# design.net
KiCad netlist of a schematic drawn in Altium Designer
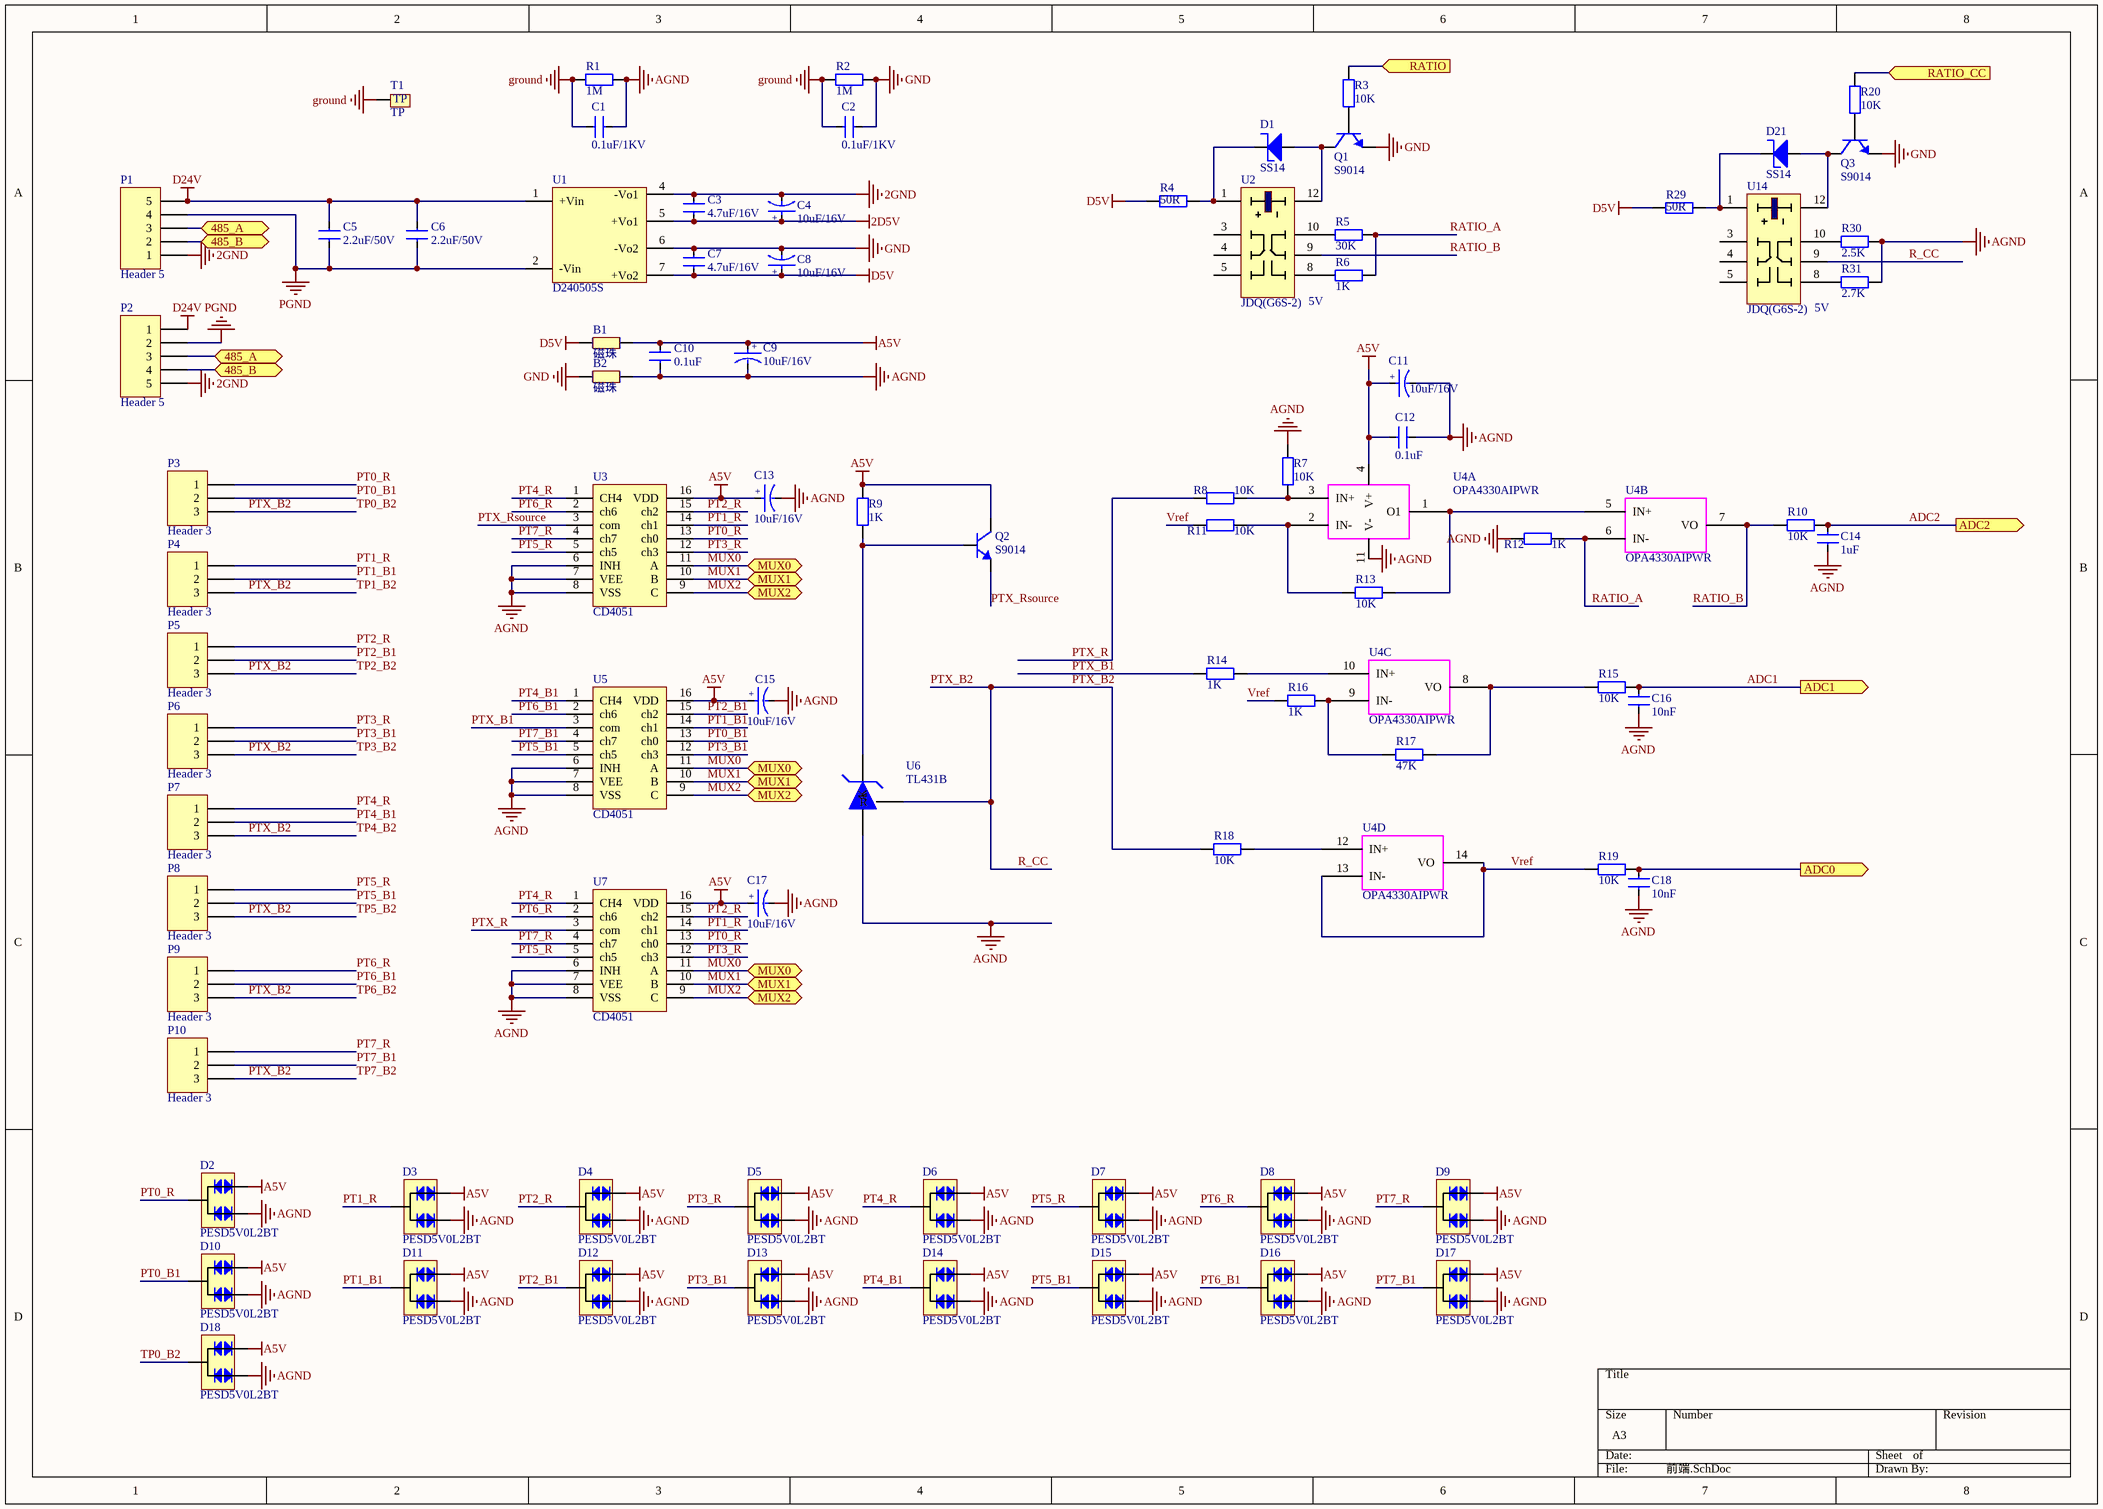
[diagram p0: 前端.SchDoc]

(export (version "E")
  (design (tool "Eeschema 10.0.6"))
  (components
    (comp (ref "B1") (value "磁珠") (footprint "0603L") (libsource (lib "lib_AD") (part "BEAD")))
    (comp (ref "B2") (value "磁珠") (footprint "0603L") (libsource (lib "lib_AD") (part "BEAD")))
    (comp (ref "C1")
      (value "0.1uF/1KV")
      (footprint "RAD0.2")
      (description "普通小电容")
      (libsource (lib "") (part "CAP_1"))
    )
    (comp (ref "C2")
      (value "0.1uF/1KV")
      (footprint "RAD0.2")
      (description "普通小电容")
      (libsource (lib "") (part "CAP_1"))
    )
    (comp (ref "C3")
      (value "4.7uF/16V")
      (footprint "0805C")
      (description "普通小电容")
      (libsource (lib "lib_AD") (part "CAP"))
    )
    (comp (ref "C4")
      (value "10uF/16V")
      (footprint "3216C")
      (description "钽电容")
      (libsource (lib "lib_AD") (part "CAP-T"))
    )
    (comp (ref "C5")
      (value "2.2uF/50V")
      (footprint "0805C")
      (description "普通小电容")
      (libsource (lib "lib_AD") (part "CAP"))
    )
    (comp (ref "C6")
      (value "2.2uF/50V")
      (footprint "0805C")
      (description "普通小电容")
      (libsource (lib "lib_AD") (part "CAP"))
    )
    (comp (ref "C7")
      (value "4.7uF/16V")
      (footprint "0805C")
      (description "普通小电容")
      (libsource (lib "lib_AD") (part "CAP"))
    )
    (comp (ref "C8")
      (value "10uF/16V")
      (footprint "3216C")
      (description "钽电容")
      (libsource (lib "lib_AD") (part "CAP-T"))
    )
    (comp (ref "C9")
      (value "10uF/16V")
      (footprint "3216C")
      (description "钽电容")
      (libsource (lib "lib_AD") (part "CAP-T"))
    )
    (comp (ref "C10")
      (value "0.1uF")
      (footprint "0603C")
      (description "普通小电容")
      (libsource (lib "lib_AD") (part "CAP"))
    )
    (comp (ref "C11")
      (value "10uF/16V")
      (footprint "3216C")
      (description "钽电容")
      (libsource (lib "lib_AD") (part "CAP-T"))
    )
    (comp (ref "C12")
      (value "0.1uF")
      (footprint "0603C")
      (description "普通小电容")
      (libsource (lib "lib_AD") (part "CAP"))
    )
    (comp (ref "C13")
      (value "10uF/16V")
      (footprint "3216C")
      (description "钽电容")
      (libsource (lib "lib_AD") (part "CAP-T"))
    )
    (comp (ref "C14")
      (value "1uF")
      (footprint "0603C")
      (description "普通小电容")
      (libsource (lib "") (part "CAP_1"))
    )
    (comp (ref "C15")
      (value "10uF/16V")
      (footprint "3216C")
      (description "钽电容")
      (libsource (lib "lib_AD") (part "CAP-T"))
    )
    (comp (ref "C16")
      (value "10nF")
      (footprint "0603C")
      (description "普通小电容")
      (libsource (lib "") (part "CAP_1"))
    )
    (comp (ref "C17")
      (value "10uF/16V")
      (footprint "3216C")
      (description "钽电容")
      (libsource (lib "lib_AD") (part "CAP-T"))
    )
    (comp (ref "C18")
      (value "10nF")
      (footprint "0603C")
      (description "普通小电容")
      (libsource (lib "") (part "CAP_1"))
    )
    (comp (ref "D1")
      (value "SS14")
      (footprint "SOD123")
      (description "肖特基二极管")
      (libsource (lib "lib_AD") (part "D-S"))
    )
    (comp (ref "D2")
      (value "PESD5V0L2BT")
      (footprint "SOT23A")
      (description "schottky diod")
      (libsource (lib "R_C_L_D") (part "PESD5V0L2BT"))
    )
    (comp (ref "D3")
      (value "PESD5V0L2BT")
      (footprint "SOT23A")
      (description "schottky diod")
      (libsource (lib "R_C_L_D") (part "PESD5V0L2BT"))
    )
    (comp (ref "D4")
      (value "PESD5V0L2BT")
      (footprint "SOT23A")
      (description "schottky diod")
      (libsource (lib "R_C_L_D") (part "PESD5V0L2BT"))
    )
    (comp (ref "D5")
      (value "PESD5V0L2BT")
      (footprint "SOT23A")
      (description "schottky diod")
      (libsource (lib "R_C_L_D") (part "PESD5V0L2BT"))
    )
    (comp (ref "D6")
      (value "PESD5V0L2BT")
      (footprint "SOT23A")
      (description "schottky diod")
      (libsource (lib "R_C_L_D") (part "PESD5V0L2BT"))
    )
    (comp (ref "D7")
      (value "PESD5V0L2BT")
      (footprint "SOT23A")
      (description "schottky diod")
      (libsource (lib "R_C_L_D") (part "PESD5V0L2BT"))
    )
    (comp (ref "D8")
      (value "PESD5V0L2BT")
      (footprint "SOT23A")
      (description "schottky diod")
      (libsource (lib "R_C_L_D") (part "PESD5V0L2BT"))
    )
    (comp (ref "D9")
      (value "PESD5V0L2BT")
      (footprint "SOT23A")
      (description "schottky diod")
      (libsource (lib "R_C_L_D") (part "PESD5V0L2BT"))
    )
    (comp (ref "D10")
      (value "PESD5V0L2BT")
      (footprint "SOT23A")
      (description "schottky diod")
      (libsource (lib "R_C_L_D") (part "PESD5V0L2BT"))
    )
    (comp (ref "D11")
      (value "PESD5V0L2BT")
      (footprint "SOT23A")
      (description "schottky diod")
      (libsource (lib "R_C_L_D") (part "PESD5V0L2BT"))
    )
    (comp (ref "D12")
      (value "PESD5V0L2BT")
      (footprint "SOT23A")
      (description "schottky diod")
      (libsource (lib "R_C_L_D") (part "PESD5V0L2BT"))
    )
    (comp (ref "D13")
      (value "PESD5V0L2BT")
      (footprint "SOT23A")
      (description "schottky diod")
      (libsource (lib "R_C_L_D") (part "PESD5V0L2BT"))
    )
    (comp (ref "D14")
      (value "PESD5V0L2BT")
      (footprint "SOT23A")
      (description "schottky diod")
      (libsource (lib "R_C_L_D") (part "PESD5V0L2BT"))
    )
    (comp (ref "D15")
      (value "PESD5V0L2BT")
      (footprint "SOT23A")
      (description "schottky diod")
      (libsource (lib "R_C_L_D") (part "PESD5V0L2BT"))
    )
    (comp (ref "D16")
      (value "PESD5V0L2BT")
      (footprint "SOT23A")
      (description "schottky diod")
      (libsource (lib "R_C_L_D") (part "PESD5V0L2BT"))
    )
    (comp (ref "D17")
      (value "PESD5V0L2BT")
      (footprint "SOT23A")
      (description "schottky diod")
      (libsource (lib "R_C_L_D") (part "PESD5V0L2BT"))
    )
    (comp (ref "D18")
      (value "PESD5V0L2BT")
      (footprint "SOT23A")
      (description "schottky diod")
      (libsource (lib "R_C_L_D") (part "PESD5V0L2BT"))
    )
    (comp (ref "D21")
      (value "SS14")
      (footprint "SOD123")
      (description "肖特基二极管")
      (libsource (lib "lib_AD") (part "D-S"))
    )
    (comp (ref "P1")
      (value "Header 5")
      (footprint "KF2DEG-3.81-5")
      (description "Header, 5-Pin")
      (fields (field (name "PUBLISHER") "Altium Limited"))
      (libsource (lib "") (part "Header 5_1"))
    )
    (comp (ref "P2")
      (value "Header 5")
      (footprint "KF2DEG-3.81-5")
      (description "Header, 5-Pin")
      (fields (field (name "PUBLISHER") "Altium Limited"))
      (libsource (lib "lib_AD") (part "Header 5"))
    )
    (comp (ref "P3")
      (value "Header 3")
      (footprint "KF2DEG-3.81-3")
      (description "Header, 3-Pin")
      (fields (field (name "PUBLISHER") "Altium Limited"))
      (libsource (lib "Header") (part "Header 3"))
    )
    (comp (ref "P4")
      (value "Header 3")
      (footprint "KF2DEG-3.81-3")
      (description "Header, 3-Pin")
      (fields (field (name "PUBLISHER") "Altium Limited"))
      (libsource (lib "Header") (part "Header 3"))
    )
    (comp (ref "P5")
      (value "Header 3")
      (footprint "KF2DEG-3.81-3")
      (description "Header, 3-Pin")
      (fields (field (name "PUBLISHER") "Altium Limited"))
      (libsource (lib "Header") (part "Header 3"))
    )
    (comp (ref "P6")
      (value "Header 3")
      (footprint "KF2DEG-3.81-3")
      (description "Header, 3-Pin")
      (fields (field (name "PUBLISHER") "Altium Limited"))
      (libsource (lib "Header") (part "Header 3"))
    )
    (comp (ref "P7")
      (value "Header 3")
      (footprint "KF2DEG-3.81-3")
      (description "Header, 3-Pin")
      (fields (field (name "PUBLISHER") "Altium Limited"))
      (libsource (lib "Header") (part "Header 3"))
    )
    (comp (ref "P8")
      (value "Header 3")
      (footprint "KF2DEG-3.81-3")
      (description "Header, 3-Pin")
      (fields (field (name "PUBLISHER") "Altium Limited"))
      (libsource (lib "Header") (part "Header 3"))
    )
    (comp (ref "P9")
      (value "Header 3")
      (footprint "KF2DEG-3.81-3")
      (description "Header, 3-Pin")
      (fields (field (name "PUBLISHER") "Altium Limited"))
      (libsource (lib "Header") (part "Header 3"))
    )
    (comp (ref "P10")
      (value "Header 3")
      (footprint "KF2DEG-3.81-3")
      (description "Header, 3-Pin")
      (fields (field (name "PUBLISHER") "Altium Limited"))
      (libsource (lib "Header") (part "Header 3"))
    )
    (comp (ref "Q1")
      (value "S9014")
      (footprint "SOT23A")
      (description "NPN三极管")
      (fields (field (name "PUBLISHER") "Altium Limited"))
      (libsource (lib "lib_AD") (part "NPN"))
    )
    (comp (ref "Q2")
      (value "S9014")
      (footprint "SOT23A")
      (description "NPN三极管")
      (fields (field (name "PUBLISHER") "Altium Limited"))
      (libsource (lib "lib_AD") (part "NPN"))
    )
    (comp (ref "Q3")
      (value "S9014")
      (footprint "SOT23A")
      (description "NPN三极管")
      (fields (field (name "PUBLISHER") "Altium Limited"))
      (libsource (lib "lib_AD") (part "NPN"))
    )
    (comp (ref "R1")
      (value "1M")
      (footprint "0805R")
      (description "普通电阻")
      (libsource (lib "") (part "RES_2"))
    )
    (comp (ref "R2")
      (value "1M")
      (footprint "0805R")
      (description "普通电阻")
      (libsource (lib "") (part "RES_2"))
    )
    (comp (ref "R3")
      (value "10K")
      (footprint "0603R")
      (description "普通电阻")
      (libsource (lib "") (part "RES_1"))
    )
    (comp (ref "R4")
      (value "50R")
      (footprint "0603R")
      (description "普通电阻")
      (libsource (lib "lib_AD") (part "RES"))
    )
    (comp (ref "R5")
      (value "30K")
      (footprint "0603R")
      (description "普通电阻")
      (libsource (lib "") (part "RES_1"))
    )
    (comp (ref "R6")
      (value "1K")
      (footprint "0603R")
      (description "普通电阻")
      (libsource (lib "") (part "RES_1"))
    )
    (comp (ref "R7")
      (value "10K")
      (footprint "0603R")
      (description "普通电阻")
      (libsource (lib "") (part "RES_1"))
    )
    (comp (ref "R8")
      (value "10K")
      (footprint "0603R")
      (description "普通电阻")
      (libsource (lib "lib_AD") (part "RES"))
    )
    (comp (ref "R9")
      (value "1K")
      (footprint "0603R")
      (description "普通电阻")
      (libsource (lib "") (part "RES_3"))
    )
    (comp (ref "R10")
      (value "10K")
      (footprint "0603R")
      (description "普通电阻")
      (libsource (lib "") (part "RES_2"))
    )
    (comp (ref "R11")
      (value "10K")
      (footprint "0603R")
      (description "普通电阻")
      (libsource (lib "lib_AD") (part "RES"))
    )
    (comp (ref "R12")
      (value "1K")
      (footprint "0603R")
      (description "普通电阻")
      (libsource (lib "lib_AD") (part "RES"))
    )
    (comp (ref "R13")
      (value "10K")
      (footprint "0603R")
      (description "普通电阻")
      (libsource (lib "lib_AD") (part "RES"))
    )
    (comp (ref "R14")
      (value "1K")
      (footprint "0603R")
      (description "普通电阻")
      (libsource (lib "lib_AD") (part "RES"))
    )
    (comp (ref "R15")
      (value "10K")
      (footprint "0603R")
      (description "普通电阻")
      (libsource (lib "") (part "RES_2"))
    )
    (comp (ref "R16")
      (value "1K")
      (footprint "0603R")
      (description "普通电阻")
      (libsource (lib "lib_AD") (part "RES"))
    )
    (comp (ref "R17")
      (value "47K")
      (footprint "0603R")
      (description "普通电阻")
      (libsource (lib "") (part "RES_2"))
    )
    (comp (ref "R18")
      (value "10K")
      (footprint "0603R")
      (description "普通电阻")
      (libsource (lib "lib_AD") (part "RES"))
    )
    (comp (ref "R19")
      (value "10K")
      (footprint "0603R")
      (description "普通电阻")
      (libsource (lib "") (part "RES_2"))
    )
    (comp (ref "R20")
      (value "10K")
      (footprint "0603R")
      (description "普通电阻")
      (libsource (lib "") (part "RES_1"))
    )
    (comp (ref "R29")
      (value "50R")
      (footprint "0603R")
      (description "普通电阻")
      (libsource (lib "lib_AD") (part "RES"))
    )
    (comp (ref "R30")
      (value "2.5K")
      (footprint "0603R")
      (description "普通电阻")
      (libsource (lib "") (part "RES_1"))
    )
    (comp (ref "R31")
      (value "2.7K")
      (footprint "0603R")
      (description "普通电阻")
      (libsource (lib "") (part "RES_1"))
    )
    (comp (ref "T1")
      (value "TP")
      (footprint "TP1")
      (description "testpoint")
      (libsource (lib "lib_AD") (part "TP"))
    )
    (comp (ref "U1")
      (value "D240505S")
      (footprint "D240505S-2W")
      (description "24V转双5V隔离DCDC")
      (libsource (lib "lib_AD") (part "D240505S-2W"))
    )
    (comp (ref "U2")
      (value "JDQ(G6S-2)")
      (footprint "JDQ-G6S-2")
      (description "继电器（G6S-2 5VDC）")
      (libsource (lib "Misc") (part "JDQ(G6S-2)"))
    )
    (comp (ref "U3")
      (value "CD4051")
      (footprint "SOP16")
      (description "模拟多路复用器")
      (libsource (lib "lib_AD") (part "CD4051"))
    )
    (comp (ref "U4")
      (value "OPA4330AIPWR")
      (footprint "TSSOP14-65")
      (description "输出轨到轨，4运放")
      (libsource (lib "lib_AD") (part "OPA4330"))
    )
    (comp (ref "U5")
      (value "CD4051")
      (footprint "SOP16")
      (description "模拟多路复用器")
      (libsource (lib "lib_AD") (part "CD4051"))
    )
    (comp (ref "U6")
      (value "TL431B")
      (footprint "SOT-89")
      (description "TL431")
      (libsource (lib "lib_AD") (part "TL431"))
    )
    (comp (ref "U7")
      (value "CD4051")
      (footprint "SOP16")
      (description "模拟多路复用器")
      (libsource (lib "lib_AD") (part "CD4051"))
    )
    (comp (ref "U14")
      (value "JDQ(G6S-2)")
      (footprint "JDQ-G6S-2")
      (description "继电器（G6S-2 5VDC）")
      (libsource (lib "Misc") (part "JDQ(G6S-2)"))
    )
  )
  (nets
    (net (code "1") (name "/485_A") (class "Default")
      (node (ref "P1") (pin "3") (pinfunction "3_3") (pintype "passive"))
      (node (ref "P2") (pin "3") (pinfunction "3_3") (pintype "passive"))
    )
    (net (code "2") (name "/485_B") (class "Default")
      (node (ref "P1") (pin "2") (pinfunction "2_2") (pintype "passive"))
      (node (ref "P2") (pin "4") (pinfunction "4_4") (pintype "passive"))
    )
    (net (code "3") (name "/ADC0") (class "Default")
      (node (ref "C18") (pin "1") (pinfunction "1_1") (pintype "passive"))
      (node (ref "R19") (pin "2") (pinfunction "2_2") (pintype "passive"))
    )
    (net (code "4") (name "/ADC1") (class "Default")
      (node (ref "C16") (pin "1") (pinfunction "1_1") (pintype "passive"))
      (node (ref "R15") (pin "2") (pinfunction "2_2") (pintype "passive"))
    )
    (net (code "5") (name "/ADC2") (class "Default")
      (node (ref "C14") (pin "1") (pinfunction "1_1") (pintype "passive"))
      (node (ref "R10") (pin "2") (pinfunction "2_2") (pintype "passive"))
    )
    (net (code "6") (name "/MUX0") (class "Default")
      (node (ref "U3") (pin "11") (pinfunction "A_11") (pintype "passive"))
      (node (ref "U5") (pin "11") (pinfunction "A_11") (pintype "passive"))
      (node (ref "U7") (pin "11") (pinfunction "A_11") (pintype "passive"))
    )
    (net (code "7") (name "/MUX1") (class "Default")
      (node (ref "U3") (pin "10") (pinfunction "B_10") (pintype "passive"))
      (node (ref "U5") (pin "10") (pinfunction "B_10") (pintype "passive"))
      (node (ref "U7") (pin "10") (pinfunction "B_10") (pintype "passive"))
    )
    (net (code "8") (name "/MUX2") (class "Default")
      (node (ref "U3") (pin "9") (pinfunction "C_9") (pintype "passive"))
      (node (ref "U5") (pin "9") (pinfunction "C_9") (pintype "passive"))
      (node (ref "U7") (pin "9") (pinfunction "C_9") (pintype "passive"))
    )
    (net (code "9") (name "/PT0_B1") (class "Default")
      (node (ref "D10") (pin "3") (pinfunction "3_3") (pintype "passive"))
      (node (ref "P3") (pin "2") (pinfunction "2_2") (pintype "passive"))
      (node (ref "U5") (pin "13") (pinfunction "ch0_13") (pintype "passive"))
    )
    (net (code "10") (name "/PT0_R") (class "Default")
      (node (ref "D2") (pin "3") (pinfunction "3_3") (pintype "passive"))
      (node (ref "P3") (pin "1") (pinfunction "1_1") (pintype "passive"))
      (node (ref "U3") (pin "13") (pinfunction "ch0_13") (pintype "passive"))
      (node (ref "U7") (pin "13") (pinfunction "ch0_13") (pintype "passive"))
    )
    (net (code "11") (name "/PT1_B1") (class "Default")
      (node (ref "D11") (pin "3") (pinfunction "3_3") (pintype "passive"))
      (node (ref "P4") (pin "2") (pinfunction "2_2") (pintype "passive"))
      (node (ref "U5") (pin "14") (pinfunction "ch1_14") (pintype "passive"))
    )
    (net (code "12") (name "/PT1_R") (class "Default")
      (node (ref "D3") (pin "3") (pinfunction "3_3") (pintype "passive"))
      (node (ref "P4") (pin "1") (pinfunction "1_1") (pintype "passive"))
      (node (ref "U3") (pin "14") (pinfunction "ch1_14") (pintype "passive"))
      (node (ref "U7") (pin "14") (pinfunction "ch1_14") (pintype "passive"))
    )
    (net (code "13") (name "/PT2_B1") (class "Default")
      (node (ref "D12") (pin "3") (pinfunction "3_3") (pintype "passive"))
      (node (ref "P5") (pin "2") (pinfunction "2_2") (pintype "passive"))
      (node (ref "U5") (pin "15") (pinfunction "ch2_15") (pintype "passive"))
    )
    (net (code "14") (name "/PT2_R") (class "Default")
      (node (ref "D4") (pin "3") (pinfunction "3_3") (pintype "passive"))
      (node (ref "P5") (pin "1") (pinfunction "1_1") (pintype "passive"))
      (node (ref "U3") (pin "15") (pinfunction "ch2_15") (pintype "passive"))
      (node (ref "U7") (pin "15") (pinfunction "ch2_15") (pintype "passive"))
    )
    (net (code "15") (name "/PT3_B1") (class "Default")
      (node (ref "D13") (pin "3") (pinfunction "3_3") (pintype "passive"))
      (node (ref "P6") (pin "2") (pinfunction "2_2") (pintype "passive"))
      (node (ref "U5") (pin "12") (pinfunction "ch3_12") (pintype "passive"))
    )
    (net (code "16") (name "/PT3_R") (class "Default")
      (node (ref "D5") (pin "3") (pinfunction "3_3") (pintype "passive"))
      (node (ref "P6") (pin "1") (pinfunction "1_1") (pintype "passive"))
      (node (ref "U3") (pin "12") (pinfunction "ch3_12") (pintype "passive"))
      (node (ref "U7") (pin "12") (pinfunction "ch3_12") (pintype "passive"))
    )
    (net (code "17") (name "/PT4_B1") (class "Default")
      (node (ref "D14") (pin "3") (pinfunction "3_3") (pintype "passive"))
      (node (ref "P7") (pin "2") (pinfunction "2_2") (pintype "passive"))
      (node (ref "U5") (pin "1") (pinfunction "CH4_1") (pintype "passive"))
    )
    (net (code "18") (name "/PT4_R") (class "Default")
      (node (ref "D6") (pin "3") (pinfunction "3_3") (pintype "passive"))
      (node (ref "P7") (pin "1") (pinfunction "1_1") (pintype "passive"))
      (node (ref "U3") (pin "1") (pinfunction "CH4_1") (pintype "passive"))
      (node (ref "U7") (pin "1") (pinfunction "CH4_1") (pintype "passive"))
    )
    (net (code "19") (name "/PT5_B1") (class "Default")
      (node (ref "D15") (pin "3") (pinfunction "3_3") (pintype "passive"))
      (node (ref "P8") (pin "2") (pinfunction "2_2") (pintype "passive"))
      (node (ref "U5") (pin "5") (pinfunction "ch5_5") (pintype "passive"))
    )
    (net (code "20") (name "/PT5_R") (class "Default")
      (node (ref "D7") (pin "3") (pinfunction "3_3") (pintype "passive"))
      (node (ref "P8") (pin "1") (pinfunction "1_1") (pintype "passive"))
      (node (ref "U3") (pin "5") (pinfunction "ch5_5") (pintype "passive"))
      (node (ref "U7") (pin "5") (pinfunction "ch5_5") (pintype "passive"))
    )
    (net (code "21") (name "/PT6_B1") (class "Default")
      (node (ref "D16") (pin "3") (pinfunction "3_3") (pintype "passive"))
      (node (ref "P9") (pin "2") (pinfunction "2_2") (pintype "passive"))
      (node (ref "U5") (pin "2") (pinfunction "ch6_2") (pintype "passive"))
    )
    (net (code "22") (name "/PT6_R") (class "Default")
      (node (ref "D8") (pin "3") (pinfunction "3_3") (pintype "passive"))
      (node (ref "P9") (pin "1") (pinfunction "1_1") (pintype "passive"))
      (node (ref "U3") (pin "2") (pinfunction "ch6_2") (pintype "passive"))
      (node (ref "U7") (pin "2") (pinfunction "ch6_2") (pintype "passive"))
    )
    (net (code "23") (name "/PT7_B1") (class "Default")
      (node (ref "D17") (pin "3") (pinfunction "3_3") (pintype "passive"))
      (node (ref "P10") (pin "2") (pinfunction "2_2") (pintype "passive"))
      (node (ref "U5") (pin "4") (pinfunction "ch7_4") (pintype "passive"))
    )
    (net (code "24") (name "/PT7_R") (class "Default")
      (node (ref "D9") (pin "3") (pinfunction "3_3") (pintype "passive"))
      (node (ref "P10") (pin "1") (pinfunction "1_1") (pintype "passive"))
      (node (ref "U3") (pin "4") (pinfunction "ch7_4") (pintype "passive"))
      (node (ref "U7") (pin "4") (pinfunction "ch7_4") (pintype "passive"))
    )
    (net (code "25") (name "/PTX_B1") (class "Default")
      (node (ref "R14") (pin "2") (pinfunction "2_2") (pintype "passive"))
      (node (ref "U5") (pin "3") (pinfunction "com_3") (pintype "passive"))
    )
    (net (code "26") (name "/PTX_B2") (class "Default")
      (node (ref "D18") (pin "3") (pinfunction "3_3") (pintype "passive"))
      (node (ref "P10") (pin "3") (pinfunction "3_3") (pintype "passive"))
      (node (ref "P3") (pin "3") (pinfunction "3_3") (pintype "passive"))
      (node (ref "P4") (pin "3") (pinfunction "3_3") (pintype "passive"))
      (node (ref "P5") (pin "3") (pinfunction "3_3") (pintype "passive"))
      (node (ref "P6") (pin "3") (pinfunction "3_3") (pintype "passive"))
      (node (ref "P7") (pin "3") (pinfunction "3_3") (pintype "passive"))
      (node (ref "P8") (pin "3") (pinfunction "3_3") (pintype "passive"))
      (node (ref "P9") (pin "3") (pinfunction "3_3") (pintype "passive"))
      (node (ref "R18") (pin "2") (pinfunction "2_2") (pintype "passive"))
      (node (ref "U14") (pin "9") (pinfunction "9_9") (pintype "passive"))
      (node (ref "U6") (pin "1") (pinfunction "R_1") (pintype "passive"))
    )
    (net (code "27") (name "/PTX_R") (class "Default")
      (node (ref "R8") (pin "2") (pinfunction "2_2") (pintype "passive"))
      (node (ref "U7") (pin "3") (pinfunction "com_3") (pintype "passive"))
    )
    (net (code "28") (name "/PTX_Rsource") (class "Default")
      (node (ref "Q2") (pin "E") (pinfunction "E_E") (pintype "passive"))
      (node (ref "U3") (pin "3") (pinfunction "com_3") (pintype "passive"))
    )
    (net (code "29") (name "/RATIO") (class "Default")
      (node (ref "R3") (pin "1") (pinfunction "1_1") (pintype "passive"))
    )
    (net (code "30") (name "/RATIO_A") (class "Default")
      (node (ref "R12") (pin "1") (pinfunction "1_1") (pintype "passive"))
      (node (ref "R5") (pin "1") (pinfunction "1_1") (pintype "passive"))
      (node (ref "R6") (pin "1") (pinfunction "1_1") (pintype "passive"))
      (node (ref "U4") (pin "6") (pinfunction "IN-_6") (pintype "passive"))
    )
    (net (code "31") (name "/RATIO_B") (class "Default")
      (node (ref "R10") (pin "1") (pinfunction "1_1") (pintype "passive"))
      (node (ref "U2") (pin "9") (pinfunction "9_9") (pintype "passive"))
      (node (ref "U4") (pin "7") (pinfunction "VO_7") (pintype "passive"))
    )
    (net (code "32") (name "/RATIO_CC") (class "Default")
      (node (ref "R20") (pin "1") (pinfunction "1_1") (pintype "passive"))
    )
    (net (code "33") (name "/Vref") (class "Default")
      (node (ref "R11") (pin "2") (pinfunction "2_2") (pintype "passive"))
      (node (ref "R16") (pin "2") (pinfunction "2_2") (pintype "passive"))
      (node (ref "R19") (pin "1") (pinfunction "1_1") (pintype "passive"))
      (node (ref "U4") (pin "13") (pinfunction "IN-_13") (pintype "passive"))
      (node (ref "U4") (pin "14") (pinfunction "VO_14") (pintype "passive"))
    )
    (net (code "34") (name "2D5V") (class "Default")
      (node (ref "C3") (pin "2") (pinfunction "2_2") (pintype "passive"))
      (node (ref "C4") (pin "1") (pinfunction "1_1") (pintype "passive"))
      (node (ref "U1") (pin "5") (pinfunction "+Vo1_5") (pintype "passive"))
    )
    (net (code "35") (name "2GND") (class "Default")
      (node (ref "C3") (pin "1") (pinfunction "1_1") (pintype "passive"))
      (node (ref "C4") (pin "2") (pinfunction "2_2") (pintype "passive"))
      (node (ref "P1") (pin "1") (pinfunction "1_1") (pintype "passive"))
      (node (ref "P2") (pin "5") (pinfunction "5_5") (pintype "passive"))
      (node (ref "U1") (pin "4") (pinfunction "-Vo1_4") (pintype "passive"))
    )
    (net (code "36") (name "A5V") (class "Default")
      (node (ref "B1") (pin "2") (pinfunction "2_2") (pintype "passive"))
      (node (ref "C10") (pin "1") (pinfunction "1_1") (pintype "passive"))
      (node (ref "C11") (pin "1") (pinfunction "1_1") (pintype "passive"))
      (node (ref "C12") (pin "2") (pinfunction "2_2") (pintype "passive"))
      (node (ref "C13") (pin "1") (pinfunction "1_1") (pintype "passive"))
      (node (ref "C15") (pin "1") (pinfunction "1_1") (pintype "passive"))
      (node (ref "C17") (pin "1") (pinfunction "1_1") (pintype "passive"))
      (node (ref "C9") (pin "1") (pinfunction "1_1") (pintype "passive"))
      (node (ref "D10") (pin "2") (pinfunction "2_2") (pintype "passive"))
      (node (ref "D11") (pin "2") (pinfunction "2_2") (pintype "passive"))
      (node (ref "D12") (pin "2") (pinfunction "2_2") (pintype "passive"))
      (node (ref "D13") (pin "2") (pinfunction "2_2") (pintype "passive"))
      (node (ref "D14") (pin "2") (pinfunction "2_2") (pintype "passive"))
      (node (ref "D15") (pin "2") (pinfunction "2_2") (pintype "passive"))
      (node (ref "D16") (pin "2") (pinfunction "2_2") (pintype "passive"))
      (node (ref "D17") (pin "2") (pinfunction "2_2") (pintype "passive"))
      (node (ref "D18") (pin "2") (pinfunction "2_2") (pintype "passive"))
      (node (ref "D2") (pin "2") (pinfunction "2_2") (pintype "passive"))
      (node (ref "D3") (pin "2") (pinfunction "2_2") (pintype "passive"))
      (node (ref "D4") (pin "2") (pinfunction "2_2") (pintype "passive"))
      (node (ref "D5") (pin "2") (pinfunction "2_2") (pintype "passive"))
      (node (ref "D6") (pin "2") (pinfunction "2_2") (pintype "passive"))
      (node (ref "D7") (pin "2") (pinfunction "2_2") (pintype "passive"))
      (node (ref "D8") (pin "2") (pinfunction "2_2") (pintype "passive"))
      (node (ref "D9") (pin "2") (pinfunction "2_2") (pintype "passive"))
      (node (ref "Q2") (pin "C") (pinfunction "C_C") (pintype "passive"))
      (node (ref "R9") (pin "2") (pinfunction "2_2") (pintype "passive"))
      (node (ref "U3") (pin "16") (pinfunction "VDD_16") (pintype "passive"))
      (node (ref "U4") (pin "4") (pinfunction "V+_4") (pintype "passive"))
      (node (ref "U5") (pin "16") (pinfunction "VDD_16") (pintype "passive"))
      (node (ref "U7") (pin "16") (pinfunction "VDD_16") (pintype "passive"))
    )
    (net (code "37") (name "AGND") (class "Default")
      (node (ref "B2") (pin "2") (pinfunction "2_2") (pintype "passive"))
      (node (ref "C1") (pin "2") (pinfunction "2_2") (pintype "passive"))
      (node (ref "C10") (pin "2") (pinfunction "2_2") (pintype "passive"))
      (node (ref "C11") (pin "2") (pinfunction "2_2") (pintype "passive"))
      (node (ref "C12") (pin "1") (pinfunction "1_1") (pintype "passive"))
      (node (ref "C13") (pin "2") (pinfunction "2_2") (pintype "passive"))
      (node (ref "C14") (pin "2") (pinfunction "2_2") (pintype "passive"))
      (node (ref "C15") (pin "2") (pinfunction "2_2") (pintype "passive"))
      (node (ref "C16") (pin "2") (pinfunction "2_2") (pintype "passive"))
      (node (ref "C17") (pin "2") (pinfunction "2_2") (pintype "passive"))
      (node (ref "C18") (pin "2") (pinfunction "2_2") (pintype "passive"))
      (node (ref "C9") (pin "2") (pinfunction "2_2") (pintype "passive"))
      (node (ref "D10") (pin "1") (pinfunction "1_1") (pintype "passive"))
      (node (ref "D11") (pin "1") (pinfunction "1_1") (pintype "passive"))
      (node (ref "D12") (pin "1") (pinfunction "1_1") (pintype "passive"))
      (node (ref "D13") (pin "1") (pinfunction "1_1") (pintype "passive"))
      (node (ref "D14") (pin "1") (pinfunction "1_1") (pintype "passive"))
      (node (ref "D15") (pin "1") (pinfunction "1_1") (pintype "passive"))
      (node (ref "D16") (pin "1") (pinfunction "1_1") (pintype "passive"))
      (node (ref "D17") (pin "1") (pinfunction "1_1") (pintype "passive"))
      (node (ref "D18") (pin "1") (pinfunction "1_1") (pintype "passive"))
      (node (ref "D2") (pin "1") (pinfunction "1_1") (pintype "passive"))
      (node (ref "D3") (pin "1") (pinfunction "1_1") (pintype "passive"))
      (node (ref "D4") (pin "1") (pinfunction "1_1") (pintype "passive"))
      (node (ref "D5") (pin "1") (pinfunction "1_1") (pintype "passive"))
      (node (ref "D6") (pin "1") (pinfunction "1_1") (pintype "passive"))
      (node (ref "D7") (pin "1") (pinfunction "1_1") (pintype "passive"))
      (node (ref "D8") (pin "1") (pinfunction "1_1") (pintype "passive"))
      (node (ref "D9") (pin "1") (pinfunction "1_1") (pintype "passive"))
      (node (ref "R1") (pin "2") (pinfunction "2_2") (pintype "passive"))
      (node (ref "R12") (pin "2") (pinfunction "2_2") (pintype "passive"))
      (node (ref "R30") (pin "1") (pinfunction "1_1") (pintype "passive"))
      (node (ref "R31") (pin "1") (pinfunction "1_1") (pintype "passive"))
      (node (ref "R7") (pin "1") (pinfunction "1_1") (pintype "passive"))
      (node (ref "U3") (pin "6") (pinfunction "INH_6") (pintype "passive"))
      (node (ref "U3") (pin "7") (pinfunction "VEE_7") (pintype "passive"))
      (node (ref "U3") (pin "8") (pinfunction "VSS_8") (pintype "passive"))
      (node (ref "U4") (pin "11") (pinfunction "V-_11") (pintype "passive"))
      (node (ref "U5") (pin "6") (pinfunction "INH_6") (pintype "passive"))
      (node (ref "U5") (pin "7") (pinfunction "VEE_7") (pintype "passive"))
      (node (ref "U5") (pin "8") (pinfunction "VSS_8") (pintype "passive"))
      (node (ref "U6") (pin "2") (pinfunction "A_2") (pintype "passive"))
      (node (ref "U7") (pin "6") (pinfunction "INH_6") (pintype "passive"))
      (node (ref "U7") (pin "7") (pinfunction "VEE_7") (pintype "passive"))
      (node (ref "U7") (pin "8") (pinfunction "VSS_8") (pintype "passive"))
    )
    (net (code "38") (name "D5V") (class "Default")
      (node (ref "B1") (pin "1") (pinfunction "1_1") (pintype "passive"))
      (node (ref "C7") (pin "2") (pinfunction "2_2") (pintype "passive"))
      (node (ref "C8") (pin "1") (pinfunction "1_1") (pintype "passive"))
      (node (ref "R29") (pin "2") (pinfunction "2_2") (pintype "passive"))
      (node (ref "R4") (pin "2") (pinfunction "2_2") (pintype "passive"))
      (node (ref "U1") (pin "7") (pinfunction "+Vo2_7") (pintype "passive"))
    )
    (net (code "39") (name "D24V") (class "Default")
      (node (ref "C5") (pin "1") (pinfunction "1_1") (pintype "passive"))
      (node (ref "C6") (pin "1") (pinfunction "1_1") (pintype "passive"))
      (node (ref "P1") (pin "5") (pinfunction "5_5") (pintype "passive"))
      (node (ref "P2") (pin "1") (pinfunction "1_1") (pintype "passive"))
      (node (ref "U1") (pin "1") (pinfunction "+Vin_1") (pintype "passive"))
    )
    (net (code "40") (name "GND") (class "Default")
      (node (ref "B2") (pin "1") (pinfunction "1_1") (pintype "passive"))
      (node (ref "C2") (pin "2") (pinfunction "2_2") (pintype "passive"))
      (node (ref "C7") (pin "1") (pinfunction "1_1") (pintype "passive"))
      (node (ref "C8") (pin "2") (pinfunction "2_2") (pintype "passive"))
      (node (ref "Q1") (pin "E") (pinfunction "E_E") (pintype "passive"))
      (node (ref "Q3") (pin "E") (pinfunction "E_E") (pintype "passive"))
      (node (ref "R2") (pin "2") (pinfunction "2_2") (pintype "passive"))
      (node (ref "U1") (pin "6") (pinfunction "-Vo2_6") (pintype "passive"))
    )
    (net (code "41") (name "Net-(D1-1)") (class "Default")
      (node (ref "D1") (pin "A") (pinfunction "1_A") (pintype "passive"))
      (node (ref "Q1") (pin "C") (pinfunction "C_C") (pintype "passive"))
      (node (ref "U2") (pin "12") (pinfunction "12_12") (pintype "passive"))
    )
    (net (code "42") (name "Net-(D1-2)") (class "Default")
      (node (ref "D1") (pin "K") (pinfunction "2_K") (pintype "passive"))
      (node (ref "R4") (pin "1") (pinfunction "1_1") (pintype "passive"))
      (node (ref "U2") (pin "1") (pinfunction "1_1") (pintype "passive"))
    )
    (net (code "43") (name "Net-(D21-1)") (class "Default")
      (node (ref "D21") (pin "A") (pinfunction "1_A") (pintype "passive"))
      (node (ref "Q3") (pin "C") (pinfunction "C_C") (pintype "passive"))
      (node (ref "U14") (pin "12") (pinfunction "12_12") (pintype "passive"))
    )
    (net (code "44") (name "Net-(D21-2)") (class "Default")
      (node (ref "D21") (pin "K") (pinfunction "2_K") (pintype "passive"))
      (node (ref "R29") (pin "1") (pinfunction "1_1") (pintype "passive"))
      (node (ref "U14") (pin "1") (pinfunction "1_1") (pintype "passive"))
    )
    (net (code "45") (name "Net-(Q1-PadB)") (class "Default")
      (node (ref "Q1") (pin "B") (pinfunction "B_B") (pintype "passive"))
      (node (ref "R3") (pin "2") (pinfunction "2_2") (pintype "passive"))
    )
    (net (code "46") (name "Net-(Q3-PadB)") (class "Default")
      (node (ref "Q3") (pin "B") (pinfunction "B_B") (pintype "passive"))
      (node (ref "R20") (pin "2") (pinfunction "2_2") (pintype "passive"))
    )
    (net (code "47") (name "Net-(R5-Pad2)") (class "Default")
      (node (ref "R5") (pin "2") (pinfunction "2_2") (pintype "passive"))
      (node (ref "U2") (pin "10") (pinfunction "10_10") (pintype "passive"))
    )
    (net (code "48") (name "Net-(R6-Pad2)") (class "Default")
      (node (ref "R6") (pin "2") (pinfunction "2_2") (pintype "passive"))
      (node (ref "U2") (pin "8") (pinfunction "8_8") (pintype "passive"))
    )
    (net (code "49") (name "Net-(R30-Pad2)") (class "Default")
      (node (ref "R30") (pin "2") (pinfunction "2_2") (pintype "passive"))
      (node (ref "U14") (pin "10") (pinfunction "10_10") (pintype "passive"))
    )
    (net (code "50") (name "Net-(R31-Pad2)") (class "Default")
      (node (ref "R31") (pin "2") (pinfunction "2_2") (pintype "passive"))
      (node (ref "U14") (pin "8") (pinfunction "8_8") (pintype "passive"))
    )
    (net (code "51") (name "Net-(U4A-IN+)") (class "Default")
      (node (ref "R7") (pin "2") (pinfunction "2_2") (pintype "passive"))
      (node (ref "R8") (pin "1") (pinfunction "1_1") (pintype "passive"))
      (node (ref "U4") (pin "3") (pinfunction "IN+_3") (pintype "passive"))
    )
    (net (code "52") (name "Net-(U4A-IN-)") (class "Default")
      (node (ref "R11") (pin "1") (pinfunction "1_1") (pintype "passive"))
      (node (ref "R13") (pin "2") (pinfunction "2_2") (pintype "passive"))
      (node (ref "U4") (pin "2") (pinfunction "IN-_2") (pintype "passive"))
    )
    (net (code "53") (name "Net-(U4A-O1)") (class "Default")
      (node (ref "R13") (pin "1") (pinfunction "1_1") (pintype "passive"))
      (node (ref "U4") (pin "1") (pinfunction "O1_1") (pintype "passive"))
      (node (ref "U4") (pin "5") (pinfunction "IN+_5") (pintype "passive"))
    )
    (net (code "54") (name "Net-(U4C-IN+)") (class "Default")
      (node (ref "R14") (pin "1") (pinfunction "1_1") (pintype "passive"))
      (node (ref "U4") (pin "10") (pinfunction "IN+_10") (pintype "passive"))
    )
    (net (code "55") (name "Net-(U4C-IN-)") (class "Default")
      (node (ref "R16") (pin "1") (pinfunction "1_1") (pintype "passive"))
      (node (ref "R17") (pin "1") (pinfunction "1_1") (pintype "passive"))
      (node (ref "U4") (pin "9") (pinfunction "IN-_9") (pintype "passive"))
    )
    (net (code "56") (name "Net-(U4C-VO)") (class "Default")
      (node (ref "R15") (pin "1") (pinfunction "1_1") (pintype "passive"))
      (node (ref "R17") (pin "2") (pinfunction "2_2") (pintype "passive"))
      (node (ref "U4") (pin "8") (pinfunction "VO_8") (pintype "passive"))
    )
    (net (code "57") (name "Net-(U4D-IN+)") (class "Default")
      (node (ref "R18") (pin "1") (pinfunction "1_1") (pintype "passive"))
      (node (ref "U4") (pin "12") (pinfunction "IN+_12") (pintype "passive"))
    )
    (net (code "58") (name "Net-(U6-K)") (class "Default")
      (node (ref "Q2") (pin "B") (pinfunction "B_B") (pintype "passive"))
      (node (ref "R9") (pin "1") (pinfunction "1_1") (pintype "passive"))
      (node (ref "U6") (pin "3") (pinfunction "K_3") (pintype "passive"))
    )
    (net (code "59") (name "PGND") (class "Default")
      (node (ref "C5") (pin "2") (pinfunction "2_2") (pintype "passive"))
      (node (ref "C6") (pin "2") (pinfunction "2_2") (pintype "passive"))
      (node (ref "P1") (pin "4") (pinfunction "4_4") (pintype "passive"))
      (node (ref "P2") (pin "2") (pinfunction "2_2") (pintype "passive"))
      (node (ref "U1") (pin "2") (pinfunction "-Vin_2") (pintype "passive"))
    )
    (net (code "60") (name "ground") (class "Default")
      (node (ref "C1") (pin "1") (pinfunction "1_1") (pintype "passive"))
      (node (ref "C2") (pin "1") (pinfunction "1_1") (pintype "passive"))
      (node (ref "R1") (pin "1") (pinfunction "1_1") (pintype "passive"))
      (node (ref "R2") (pin "1") (pinfunction "1_1") (pintype "passive"))
      (node (ref "T1") (pin "1") (pinfunction "1_1") (pintype "passive"))
    )
    (net (code "61") (name "unconnected-(U2-Pad3)") (class "Default")
      (node (ref "U2") (pin "3") (pinfunction "3_3") (pintype "passive"))
    )
    (net (code "62") (name "unconnected-(U2-Pad4)") (class "Default")
      (node (ref "U2") (pin "4") (pinfunction "4_4") (pintype "passive"))
    )
    (net (code "63") (name "unconnected-(U2-Pad5)") (class "Default")
      (node (ref "U2") (pin "5") (pinfunction "5_5") (pintype "passive"))
    )
    (net (code "64") (name "unconnected-(U14-Pad3)") (class "Default")
      (node (ref "U14") (pin "3") (pinfunction "3_3") (pintype "passive"))
    )
    (net (code "65") (name "unconnected-(U14-Pad4)") (class "Default")
      (node (ref "U14") (pin "4") (pinfunction "4_4") (pintype "passive"))
    )
    (net (code "66") (name "unconnected-(U14-Pad5)") (class "Default")
      (node (ref "U14") (pin "5") (pinfunction "5_5") (pintype "passive"))
    )
  )
)
